# Innlevering.net
KiCad netlist of a schematic drawn in EAGLE
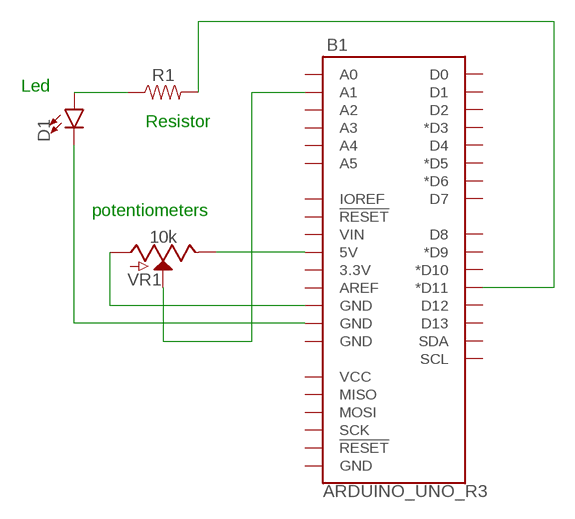
[diagram p0: schematic, sheet 1]

(export (version "E")
  (design (tool "Eeschema 10.0.6"))
  (components
    (comp (ref "B1")
      (value "ARDUINO_UNO_R3")
      (footprint "eagle-import:ARDUINO_R3")
      (libsource (lib "eagle-import") (part "ARDUINO_UNO_R3"))
    )
    (comp (ref "D1")
      (value "LED-3MM-NO_SILK")
      (footprint "eagle-import:LED_3MM-NS")
      (libsource (lib "eagle-import") (part "LED-3MM-NO_SILK"))
    )
    (comp (ref "R1")
      (value "RESISTORAXIAL-0.3")
      (footprint "eagle-import:AXIAL-0.3")
      (libsource (lib "eagle-import") (part "RESISTORAXIAL-0.3"))
    )
    (comp (ref "VR1")
      (value "10k")
      (footprint "eagle-import:POT-PTH-ALPS")
      (libsource (lib "eagle-import") (part "POTENTIOMETER-PTH-9MM-1/20W-20%"))
    )
  )
  (nets
    (net (code "1") (name "Net-(B1-*D11)") (class "Default")
      (node (ref "B1") (pin "D11") (pinfunction "*D11_D11") (pintype "bidirectional"))
      (node (ref "R1") (pin "P$2") (pinfunction "2_P$2") (pintype "passive"))
    )
    (net (code "2") (name "Net-(D1-C)") (class "Default")
      (node (ref "B1") (pin "GND@3") (pinfunction "GND_GND@3") (pintype "bidirectional"))
      (node (ref "D1") (pin "K") (pinfunction "C_K") (pintype "passive"))
    )
    (net (code "3") (name "Net-(R1-1)") (class "Default")
      (node (ref "D1") (pin "A") (pinfunction "A_A") (pintype "passive"))
      (node (ref "R1") (pin "P$1") (pinfunction "1_P$1") (pintype "passive"))
    )
    (net (code "4") (name "Net-(VR1-A)") (class "Default")
      (node (ref "B1") (pin "GND@4") (pinfunction "GND_GND@4") (pintype "bidirectional"))
      (node (ref "VR1") (pin "P$3") (pinfunction "A_P$3") (pintype "passive"))
    )
    (net (code "5") (name "Net-(VR1-E)") (class "Default")
      (node (ref "B1") (pin "5V") (pinfunction "5V_5V") (pintype "bidirectional"))
      (node (ref "VR1") (pin "P$1") (pinfunction "E_P$1") (pintype "passive"))
    )
    (net (code "6") (name "Net-(VR1-S)") (class "Default")
      (node (ref "B1") (pin "A1") (pinfunction "A1_A1") (pintype "bidirectional"))
      (node (ref "VR1") (pin "P$2") (pinfunction "S_P$2") (pintype "passive"))
    )
    (net (code "7") (name "unconnected-(B1-*D3-PadD3)") (class "Default")
      (node (ref "B1") (pin "D3") (pinfunction "*D3_D3") (pintype "bidirectional"))
    )
    (net (code "8") (name "unconnected-(B1-*D5-PadD5)") (class "Default")
      (node (ref "B1") (pin "D5") (pinfunction "*D5_D5") (pintype "bidirectional"))
    )
    (net (code "9") (name "unconnected-(B1-*D6-PadD6)") (class "Default")
      (node (ref "B1") (pin "D6") (pinfunction "*D6_D6") (pintype "bidirectional"))
    )
    (net (code "10") (name "unconnected-(B1-*D9-PadD9)") (class "Default")
      (node (ref "B1") (pin "D9") (pinfunction "*D9_D9") (pintype "bidirectional"))
    )
    (net (code "11") (name "unconnected-(B1-*D10-PadD10)") (class "Default")
      (node (ref "B1") (pin "D10") (pinfunction "*D10_D10") (pintype "bidirectional"))
    )
    (net (code "12") (name "unconnected-(B1-GND-PadGND@1)") (class "Default")
      (node (ref "B1") (pin "GND@1") (pinfunction "GND_GND@1") (pintype "bidirectional"))
    )
    (net (code "13") (name "unconnected-(B1-GND-PadGND@2)") (class "Default")
      (node (ref "B1") (pin "GND@2") (pinfunction "GND_GND@2") (pintype "bidirectional"))
    )
    (net (code "14") (name "unconnected-(B1-Pad3.3V)") (class "Default")
      (node (ref "B1") (pin "3.3V") (pinfunction "3.3V_3.3V") (pintype "bidirectional"))
    )
    (net (code "15") (name "unconnected-(B1-PadA0)") (class "Default")
      (node (ref "B1") (pin "A0") (pinfunction "A0_A0") (pintype "bidirectional"))
    )
    (net (code "16") (name "unconnected-(B1-PadA2)") (class "Default")
      (node (ref "B1") (pin "A2") (pinfunction "A2_A2") (pintype "bidirectional"))
    )
    (net (code "17") (name "unconnected-(B1-PadA3)") (class "Default")
      (node (ref "B1") (pin "A3") (pinfunction "A3_A3") (pintype "bidirectional"))
    )
    (net (code "18") (name "unconnected-(B1-PadA4)") (class "Default")
      (node (ref "B1") (pin "A4") (pinfunction "A4_A4") (pintype "bidirectional"))
    )
    (net (code "19") (name "unconnected-(B1-PadA5)") (class "Default")
      (node (ref "B1") (pin "A5") (pinfunction "A5_A5") (pintype "bidirectional"))
    )
    (net (code "20") (name "unconnected-(B1-PadAREF)") (class "Default")
      (node (ref "B1") (pin "AREF") (pinfunction "AREF_AREF") (pintype "bidirectional"))
    )
    (net (code "21") (name "unconnected-(B1-PadD0)") (class "Default")
      (node (ref "B1") (pin "D0") (pinfunction "D0_D0") (pintype "bidirectional"))
    )
    (net (code "22") (name "unconnected-(B1-PadD1)") (class "Default")
      (node (ref "B1") (pin "D1") (pinfunction "D1_D1") (pintype "bidirectional"))
    )
    (net (code "23") (name "unconnected-(B1-PadD2)") (class "Default")
      (node (ref "B1") (pin "D2") (pinfunction "D2_D2") (pintype "bidirectional"))
    )
    (net (code "24") (name "unconnected-(B1-PadD4)") (class "Default")
      (node (ref "B1") (pin "D4") (pinfunction "D4_D4") (pintype "bidirectional"))
    )
    (net (code "25") (name "unconnected-(B1-PadD7)") (class "Default")
      (node (ref "B1") (pin "D7") (pinfunction "D7_D7") (pintype "bidirectional"))
    )
    (net (code "26") (name "unconnected-(B1-PadD8)") (class "Default")
      (node (ref "B1") (pin "D8") (pinfunction "D8_D8") (pintype "bidirectional"))
    )
    (net (code "27") (name "unconnected-(B1-PadD12)") (class "Default")
      (node (ref "B1") (pin "D12") (pinfunction "D12_D12") (pintype "bidirectional"))
    )
    (net (code "28") (name "unconnected-(B1-PadD13)") (class "Default")
      (node (ref "B1") (pin "D13") (pinfunction "D13_D13") (pintype "bidirectional"))
    )
    (net (code "29") (name "unconnected-(B1-PadIOREF)") (class "Default")
      (node (ref "B1") (pin "IOREF") (pinfunction "IOREF_IOREF") (pintype "bidirectional"))
    )
    (net (code "30") (name "unconnected-(B1-PadMISO)") (class "Default")
      (node (ref "B1") (pin "MISO") (pinfunction "MISO_MISO") (pintype "bidirectional"))
    )
    (net (code "31") (name "unconnected-(B1-PadMOSI)") (class "Default")
      (node (ref "B1") (pin "MOSI") (pinfunction "MOSI_MOSI") (pintype "bidirectional"))
    )
    (net (code "32") (name "unconnected-(B1-PadSCK)") (class "Default")
      (node (ref "B1") (pin "SCK") (pinfunction "SCK_SCK") (pintype "bidirectional"))
    )
    (net (code "33") (name "unconnected-(B1-PadSCL)") (class "Default")
      (node (ref "B1") (pin "SCL") (pinfunction "SCL_SCL") (pintype "bidirectional"))
    )
    (net (code "34") (name "unconnected-(B1-PadSDA)") (class "Default")
      (node (ref "B1") (pin "SDA") (pinfunction "SDA_SDA") (pintype "bidirectional"))
    )
    (net (code "35") (name "unconnected-(B1-PadVCC)") (class "Default")
      (node (ref "B1") (pin "VCC") (pinfunction "VCC_VCC") (pintype "bidirectional"))
    )
    (net (code "36") (name "unconnected-(B1-PadVIN)") (class "Default")
      (node (ref "B1") (pin "VIN") (pinfunction "VIN_VIN") (pintype "bidirectional"))
    )
    (net (code "37") (name "unconnected-(B1-~{RESET}-PadRESET@1)") (class "Default")
      (node (ref "B1") (pin "RESET@1") (pinfunction "~{RESET}_RESET@1") (pintype "bidirectional"))
    )
    (net (code "38") (name "unconnected-(B1-~{RESET}-PadRESET@2)") (class "Default")
      (node (ref "B1") (pin "RESET@2") (pinfunction "~{RESET}_RESET@2") (pintype "bidirectional"))
    )
  )
)
